# controller_board.net
KiCad netlist of a schematic drawn in EAGLE
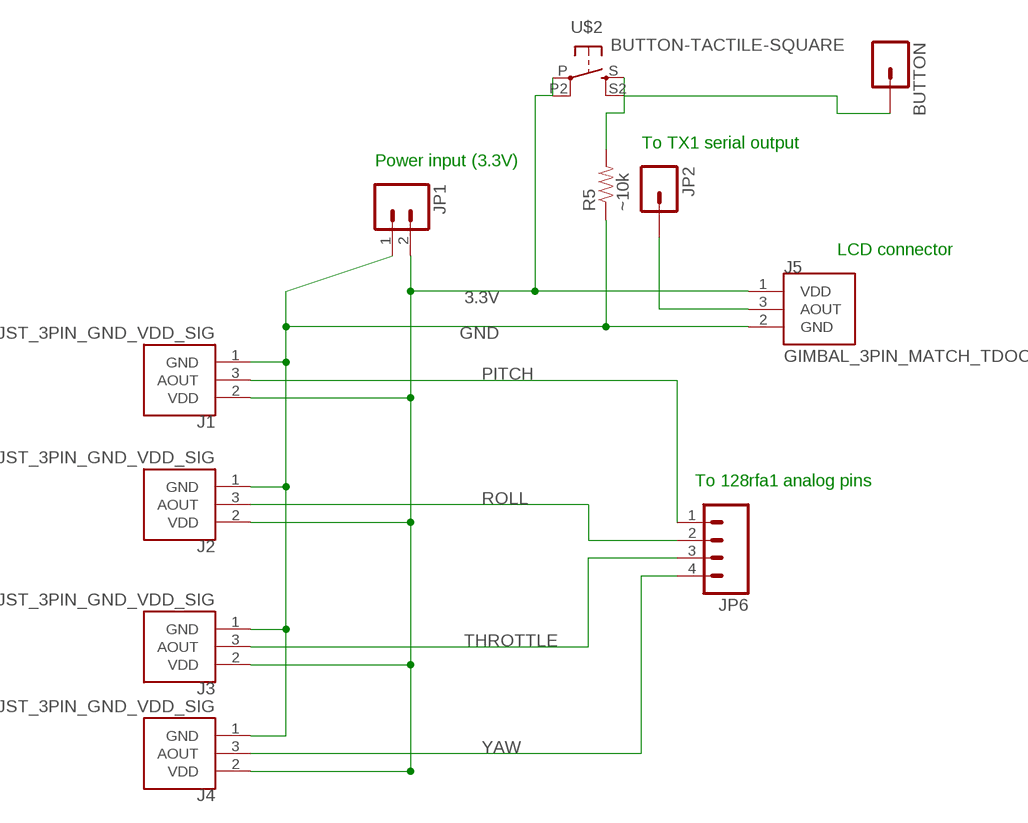
[diagram p0: schematic, sheet 1]

(export (version "E")
  (design (tool "Eeschema 10.0.6"))
  (components
    (comp (ref "BUTTON")
      (value "M01PTH")
      (footprint "eagle-import:1X01")
      (libsource (lib "eagle-import") (part "M01PTH"))
    )
    (comp (ref "J1")
      (value "JST_3PIN_GND_VDD_SIG")
      (footprint "eagle-import:JST-3-PTH-REVERSE")
      (libsource (lib "eagle-import") (part "JST_3PIN_GND_VDD_SIG"))
    )
    (comp (ref "J2")
      (value "JST_3PIN_GND_VDD_SIG")
      (footprint "eagle-import:JST-3-PTH-REVERSE")
      (libsource (lib "eagle-import") (part "JST_3PIN_GND_VDD_SIG"))
    )
    (comp (ref "J3")
      (value "JST_3PIN_GND_VDD_SIG")
      (footprint "eagle-import:JST-3-PTH-REVERSE")
      (libsource (lib "eagle-import") (part "JST_3PIN_GND_VDD_SIG"))
    )
    (comp (ref "J4")
      (value "JST_3PIN_GND_VDD_SIG")
      (footprint "eagle-import:JST-3-PTH-REVERSE")
      (libsource (lib "eagle-import") (part "JST_3PIN_GND_VDD_SIG"))
    )
    (comp (ref "J5")
      (value "GIMBAL_3PIN_MATCH_TDOCU")
      (footprint "eagle-import:JST-3-PTH")
      (libsource (lib "eagle-import") (part "GIMBAL_3PIN_MATCH_TDOCU"))
    )
    (comp (ref "JP1")
      (value "M021X02_NO_SILK")
      (footprint "eagle-import:1X02_NO_SILK")
      (libsource (lib "eagle-import") (part "M021X02_NO_SILK"))
    )
    (comp (ref "JP2")
      (value "M01PTH")
      (footprint "eagle-import:1X01")
      (libsource (lib "eagle-import") (part "M01PTH"))
    )
    (comp (ref "JP6")
      (value "M04PTH")
      (footprint "eagle-import:1X04")
      (libsource (lib "eagle-import") (part "M04PTH"))
    )
    (comp (ref "R5")
      (value "~10k")
      (footprint "eagle-import:AXIAL-0.4")
      (libsource (lib "eagle-import") (part "RESISTORPTH-1/4W"))
    )
    (comp (ref "U$2")
      (value "BUTTON-TACTILE-SQUARE")
      (footprint "eagle-import:BUTTON-TACTILE-SQUARE-ADAFRUIT1010")
      (libsource (lib "eagle-import") (part "BUTTON-TACTILE-SQUARE"))
    )
  )
  (nets
    (net (code "1") (name "/3.3V") (class "Default")
      (node (ref "J1") (pin "2") (pinfunction "VDD_2") (pintype "power_in"))
      (node (ref "J2") (pin "2") (pinfunction "VDD_2") (pintype "power_in"))
      (node (ref "J3") (pin "2") (pinfunction "VDD_2") (pintype "power_in"))
      (node (ref "J4") (pin "2") (pinfunction "VDD_2") (pintype "power_in"))
      (node (ref "J5") (pin "1") (pinfunction "VDD_1") (pintype "power_in"))
      (node (ref "JP1") (pin "2") (pinfunction "2_2") (pintype "passive"))
      (node (ref "U$2") (pin "P") (pinfunction "P_P") (pintype "passive"))
      (node (ref "U$2") (pin "P2") (pinfunction "P1_P2") (pintype "passive"))
    )
    (net (code "2") (name "/GND") (class "Default")
      (node (ref "J1") (pin "1") (pinfunction "GND_1") (pintype "power_in"))
      (node (ref "J2") (pin "1") (pinfunction "GND_1") (pintype "power_in"))
      (node (ref "J3") (pin "1") (pinfunction "GND_1") (pintype "power_in"))
      (node (ref "J4") (pin "1") (pinfunction "GND_1") (pintype "power_in"))
      (node (ref "J5") (pin "2") (pinfunction "GND_2") (pintype "power_in"))
      (node (ref "JP1") (pin "1") (pinfunction "1_1") (pintype "passive"))
      (node (ref "R5") (pin "P$1") (pinfunction "1_P$1") (pintype "passive"))
    )
    (net (code "3") (name "/PITCH") (class "Default")
      (node (ref "J1") (pin "3") (pinfunction "AOUT_3") (pintype "bidirectional"))
      (node (ref "JP6") (pin "1") (pinfunction "1_1") (pintype "passive"))
    )
    (net (code "4") (name "/ROLL") (class "Default")
      (node (ref "J2") (pin "3") (pinfunction "AOUT_3") (pintype "bidirectional"))
      (node (ref "JP6") (pin "2") (pinfunction "2_2") (pintype "passive"))
    )
    (net (code "5") (name "/THROTTLE") (class "Default")
      (node (ref "J3") (pin "3") (pinfunction "AOUT_3") (pintype "bidirectional"))
      (node (ref "JP6") (pin "3") (pinfunction "3_3") (pintype "passive"))
    )
    (net (code "6") (name "/YAW") (class "Default")
      (node (ref "J4") (pin "3") (pinfunction "AOUT_3") (pintype "bidirectional"))
      (node (ref "JP6") (pin "4") (pinfunction "4_4") (pintype "passive"))
    )
    (net (code "7") (name "Net-(J5-AOUT)") (class "Default")
      (node (ref "J5") (pin "3") (pinfunction "AOUT_3") (pintype "bidirectional"))
      (node (ref "JP2") (pin "1") (pinfunction "1_1") (pintype "passive"))
    )
    (net (code "8") (name "Net-(R5-2)") (class "Default")
      (node (ref "BUTTON") (pin "1") (pinfunction "1_1") (pintype "passive"))
      (node (ref "R5") (pin "P$2") (pinfunction "2_P$2") (pintype "passive"))
      (node (ref "U$2") (pin "S") (pinfunction "S_S") (pintype "passive"))
      (node (ref "U$2") (pin "S2") (pinfunction "S1_S2") (pintype "passive"))
    )
  )
)
